# Top.net
KiCad netlist of a schematic drawn in Altium Designer
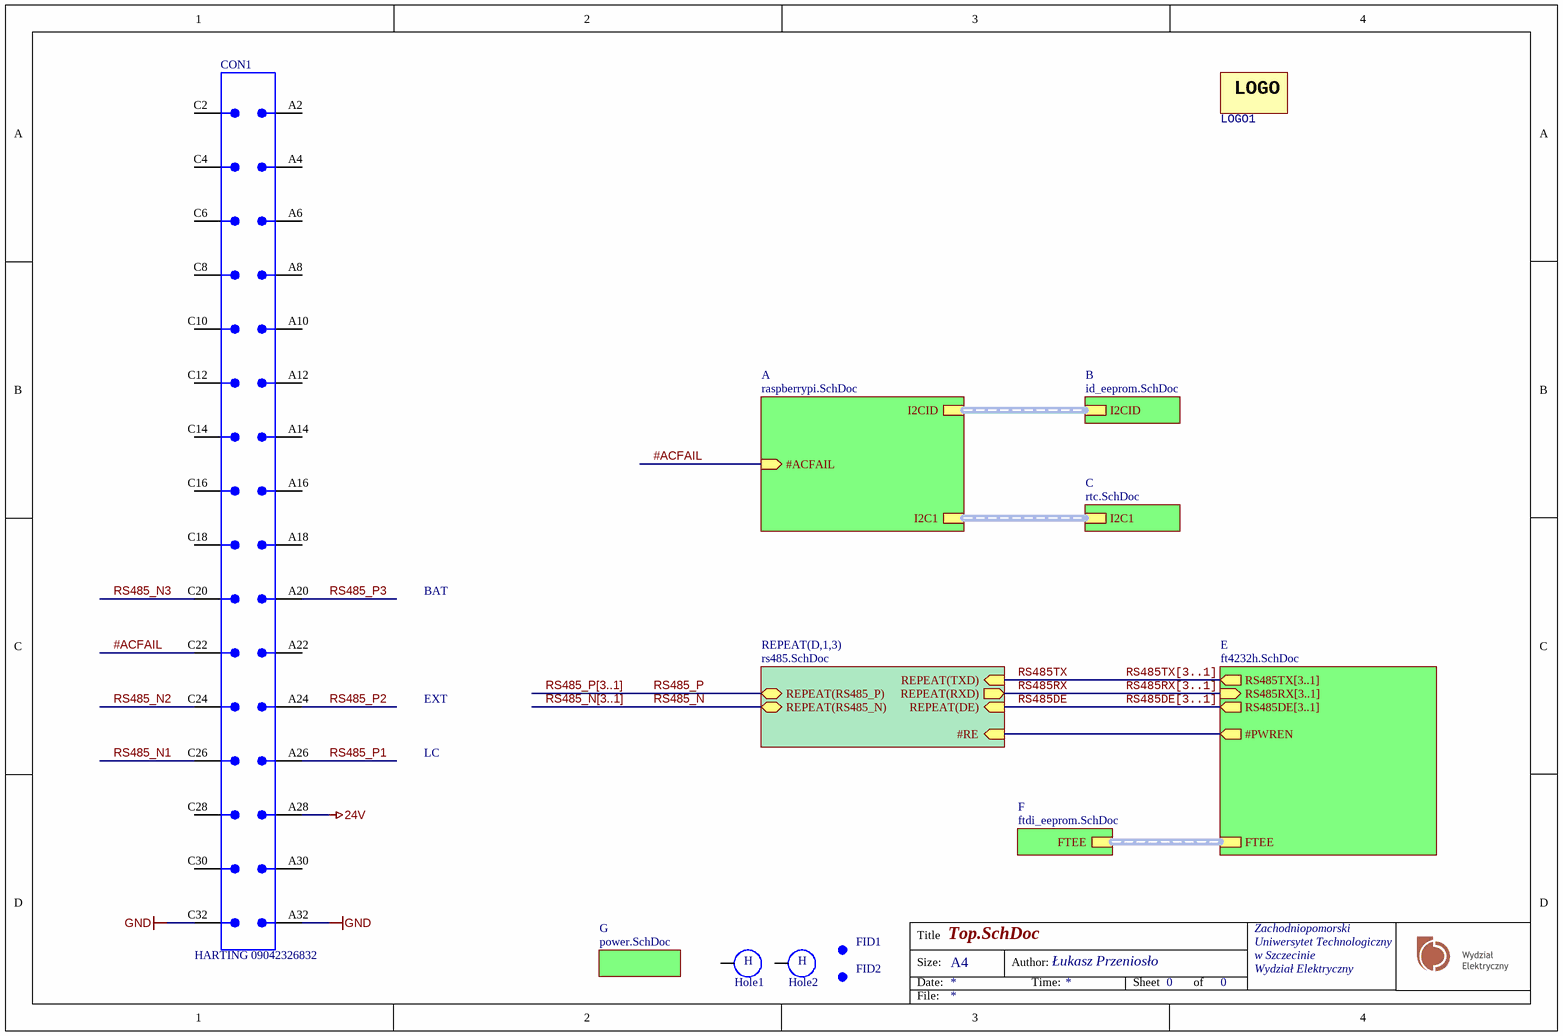
[diagram p0: Top.SchDoc]

(export (version "E")
  (design (tool "Eeschema 10.0.6"))
  (components
    (comp (ref "CON1")
      (value "HARTING 09042326832")
      (footprint "HARTING 09041326921")
      (description "Board-to-Board Connector, Eurocard VME, Vertical, 3-Row, 32-Position,")
      (libsource (lib "Connectors") (part "HARTING_09042326832"))
    )
    (comp (ref "FID1")
      (value "Fiducial")
      (footprint "Fid Round")
      (description "round fiducial")
      (libsource (lib "Mechatronic") (part "FID ROUND"))
    )
    (comp (ref "FID2")
      (value "Fiducial")
      (footprint "Fid Round")
      (description "round fiducial")
      (libsource (lib "Mechatronic") (part "FID ROUND"))
    )
    (comp (ref "Hole1")
      (value "Hole")
      (footprint "Hole-3/6")
      (libsource (lib "my_various_devices") (part "HOLE_"))
    )
    (comp (ref "Hole2")
      (value "Hole")
      (footprint "Hole-3/6")
      (libsource (lib "my_various_devices") (part "HOLE_"))
    )
    (comp (ref "LOGO1")
      (value "Logo")
      (footprint "LOGO_BEMKO")
      (libsource (lib "my_various_devices") (part "Logo"))
    )
  )
  (nets
    (net (code "10") (name "/#ACFAIL") (class "Default")
      (node (ref "CON1") (pin "C22") (pinfunction "C22_C22") (pintype "passive"))
    )
    (net (code "22") (name "/RS485_N1") (class "Default")
      (node (ref "CON1") (pin "C26") (pinfunction "C26_C26") (pintype "passive"))
    )
    (net (code "23") (name "/RS485_N2") (class "Default")
      (node (ref "CON1") (pin "C24") (pinfunction "C24_C24") (pintype "passive"))
    )
    (net (code "24") (name "/RS485_N3") (class "Default")
      (node (ref "CON1") (pin "C20") (pinfunction "C20_C20") (pintype "passive"))
    )
    (net (code "27") (name "/RS485_P1") (class "Default")
      (node (ref "CON1") (pin "A26") (pinfunction "A26_A26") (pintype "passive"))
    )
    (net (code "28") (name "/RS485_P2") (class "Default")
      (node (ref "CON1") (pin "A24") (pinfunction "A24_A24") (pintype "passive"))
    )
    (net (code "29") (name "/RS485_P3") (class "Default")
      (node (ref "CON1") (pin "A20") (pinfunction "A20_A20") (pintype "passive"))
    )
    (net (code "31") (name "24V") (class "Default")
      (node (ref "CON1") (pin "A28") (pinfunction "A28_A28") (pintype "passive"))
    )
    (net (code "32") (name "GND") (class "Default")
      (node (ref "CON1") (pin "A32") (pinfunction "A32_A32") (pintype "passive"))
      (node (ref "CON1") (pin "C32") (pinfunction "C32_C32") (pintype "passive"))
    )
    (net (code "33") (name "unconnected-(CON1-PadA2)") (class "Default")
      (node (ref "CON1") (pin "A2") (pinfunction "A2_A2") (pintype "passive"))
    )
    (net (code "34") (name "unconnected-(CON1-PadA4)") (class "Default")
      (node (ref "CON1") (pin "A4") (pinfunction "A4_A4") (pintype "passive"))
    )
    (net (code "35") (name "unconnected-(CON1-PadA6)") (class "Default")
      (node (ref "CON1") (pin "A6") (pinfunction "A6_A6") (pintype "passive"))
    )
    (net (code "36") (name "unconnected-(CON1-PadA8)") (class "Default")
      (node (ref "CON1") (pin "A8") (pinfunction "A8_A8") (pintype "passive"))
    )
    (net (code "37") (name "unconnected-(CON1-PadA10)") (class "Default")
      (node (ref "CON1") (pin "A10") (pinfunction "A10_A10") (pintype "passive"))
    )
    (net (code "38") (name "unconnected-(CON1-PadA12)") (class "Default")
      (node (ref "CON1") (pin "A12") (pinfunction "A12_A12") (pintype "passive"))
    )
    (net (code "39") (name "unconnected-(CON1-PadA14)") (class "Default")
      (node (ref "CON1") (pin "A14") (pinfunction "A14_A14") (pintype "passive"))
    )
    (net (code "40") (name "unconnected-(CON1-PadA16)") (class "Default")
      (node (ref "CON1") (pin "A16") (pinfunction "A16_A16") (pintype "passive"))
    )
    (net (code "41") (name "unconnected-(CON1-PadA18)") (class "Default")
      (node (ref "CON1") (pin "A18") (pinfunction "A18_A18") (pintype "passive"))
    )
    (net (code "42") (name "unconnected-(CON1-PadA22)") (class "Default")
      (node (ref "CON1") (pin "A22") (pinfunction "A22_A22") (pintype "passive"))
    )
    (net (code "43") (name "unconnected-(CON1-PadA30)") (class "Default")
      (node (ref "CON1") (pin "A30") (pinfunction "A30_A30") (pintype "passive"))
    )
    (net (code "44") (name "unconnected-(CON1-PadC2)") (class "Default")
      (node (ref "CON1") (pin "C2") (pinfunction "C2_C2") (pintype "passive"))
    )
    (net (code "45") (name "unconnected-(CON1-PadC4)") (class "Default")
      (node (ref "CON1") (pin "C4") (pinfunction "C4_C4") (pintype "passive"))
    )
    (net (code "46") (name "unconnected-(CON1-PadC6)") (class "Default")
      (node (ref "CON1") (pin "C6") (pinfunction "C6_C6") (pintype "passive"))
    )
    (net (code "47") (name "unconnected-(CON1-PadC8)") (class "Default")
      (node (ref "CON1") (pin "C8") (pinfunction "C8_C8") (pintype "passive"))
    )
    (net (code "48") (name "unconnected-(CON1-PadC10)") (class "Default")
      (node (ref "CON1") (pin "C10") (pinfunction "C10_C10") (pintype "passive"))
    )
    (net (code "49") (name "unconnected-(CON1-PadC12)") (class "Default")
      (node (ref "CON1") (pin "C12") (pinfunction "C12_C12") (pintype "passive"))
    )
    (net (code "50") (name "unconnected-(CON1-PadC14)") (class "Default")
      (node (ref "CON1") (pin "C14") (pinfunction "C14_C14") (pintype "passive"))
    )
    (net (code "51") (name "unconnected-(CON1-PadC16)") (class "Default")
      (node (ref "CON1") (pin "C16") (pinfunction "C16_C16") (pintype "passive"))
    )
    (net (code "52") (name "unconnected-(CON1-PadC18)") (class "Default")
      (node (ref "CON1") (pin "C18") (pinfunction "C18_C18") (pintype "passive"))
    )
    (net (code "53") (name "unconnected-(CON1-PadC28)") (class "Default")
      (node (ref "CON1") (pin "C28") (pinfunction "C28_C28") (pintype "passive"))
    )
    (net (code "54") (name "unconnected-(CON1-PadC30)") (class "Default")
      (node (ref "CON1") (pin "C30") (pinfunction "C30_C30") (pintype "passive"))
    )
    (net (code "55") (name "unconnected-(Hole1-Pad1)") (class "Default")
      (node (ref "Hole1") (pin "1") (pinfunction "1_1") (pintype "passive"))
    )
    (net (code "56") (name "unconnected-(Hole2-Pad1)") (class "Default")
      (node (ref "Hole2") (pin "1") (pinfunction "1_1") (pintype "passive"))
    )
  )
)
